# bmsMaster_conn.net
KiCad netlist of a schematic drawn in Altium Designer
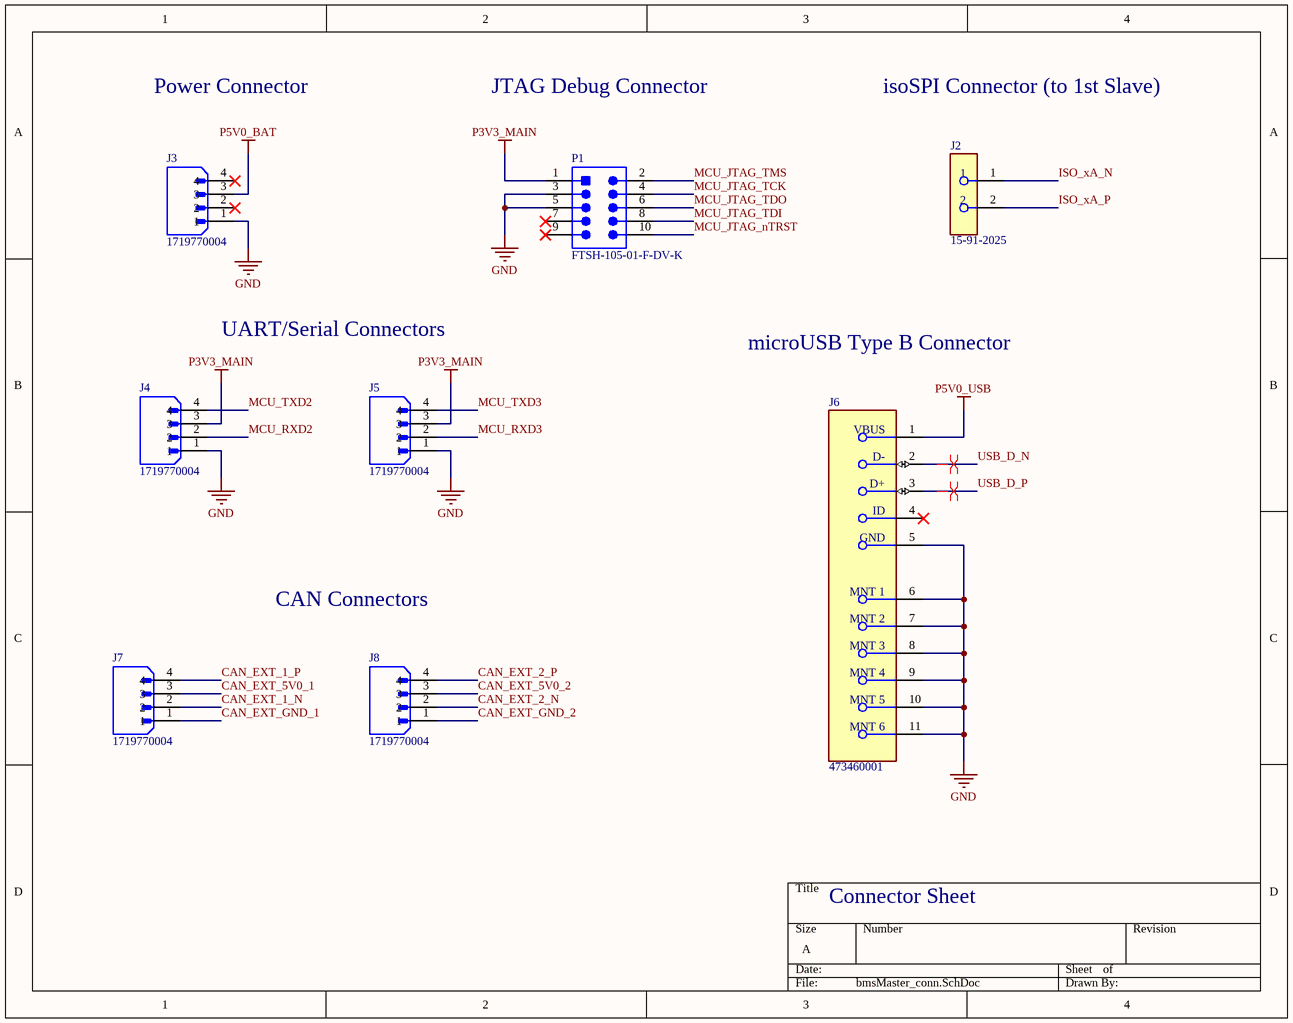
[diagram p0: bmsMaster_conn.SchDoc]

(export (version "E")
  (design (tool "Eeschema 10.0.6"))
  (components
    (comp (ref "J2")
      (value "15-91-2025")
      (footprint "FP-15-91-2025-MFG")
      (description "CONN HEADER SMD R/A 2POS 2.54MM")
      (libsource (lib "Altium Content Vault") (part "3ddab50f66188bb7952c54a1b76274c"))
    )
    (comp (ref "J3")
      (value "1719770004")
      (footprint "171977-0004:MOLEX_1719770004")
      (fields (field (name "MF") "{'manufacturer': u'Molex'}"))
      (libsource (lib "*") (part "1719770004"))
    )
    (comp (ref "J4")
      (value "1719770004")
      (footprint "171977-0004:MOLEX_1719770004")
      (fields (field (name "MF") "{'manufacturer': u'Molex'}"))
      (libsource (lib "*") (part "1719770004"))
    )
    (comp (ref "J5")
      (value "1719770004")
      (footprint "171977-0004:MOLEX_1719770004")
      (fields (field (name "MF") "{'manufacturer': u'Molex'}"))
      (libsource (lib "*") (part "1719770004"))
    )
    (comp (ref "J6")
      (value "473460001")
      (footprint "FP-473460001-MFG")
      (description "USB - micro B USB 2.0 Receptacle Connector 5 Position Surface Mount, Right Angle")
      (fields (field (name "OCTOPART") "https://octopart.com/47346-0001-molex-7164928"))
      (libsource (lib "Altium Content Vault") (part "53ae1f1d9b557310b43ca686e5bb76a"))
    )
    (comp (ref "J7")
      (value "1719770004")
      (footprint "171977-0004:MOLEX_1719770004")
      (fields (field (name "MF") "{'manufacturer': u'Molex'}"))
      (libsource (lib "*") (part "1719770004"))
    )
    (comp (ref "J8")
      (value "1719770004")
      (footprint "171977-0004:MOLEX_1719770004")
      (fields (field (name "MF") "{'manufacturer': u'Molex'}"))
      (libsource (lib "*") (part "1719770004"))
    )
    (comp (ref "P1")
      (value "FTSH-105-01-F-DV-K")
      (footprint "SMTC-FTSH-105-01-L-DV-K_V")
      (description "Male Header, Pitch 1.27 mm, 2 x 5 Position, Height 6.12 mm, RoHS, Tube")
      (fields (field (name "MANUFACTURER") "Samtec"))
      (libsource (lib "Altium Content Vault") (part "CN-2P-M-R10"))
    )
  )
  (nets
    (net (code "1") (name "/CAN_EXT_1_N") (class "Default")
      (node (ref "J7") (pin "2") (pinfunction "2_2") (pintype "passive"))
    )
    (net (code "2") (name "/CAN_EXT_1_P") (class "Default")
      (node (ref "J7") (pin "4") (pinfunction "4_4") (pintype "passive"))
    )
    (net (code "3") (name "/CAN_EXT_2_N") (class "Default")
      (node (ref "J8") (pin "2") (pinfunction "2_2") (pintype "passive"))
    )
    (net (code "4") (name "/CAN_EXT_2_P") (class "Default")
      (node (ref "J8") (pin "4") (pinfunction "4_4") (pintype "passive"))
    )
    (net (code "5") (name "/CAN_EXT_5V0_1") (class "Default")
      (node (ref "J7") (pin "3") (pinfunction "3_3") (pintype "passive"))
    )
    (net (code "6") (name "/CAN_EXT_5V0_2") (class "Default")
      (node (ref "J8") (pin "3") (pinfunction "3_3") (pintype "passive"))
    )
    (net (code "7") (name "/CAN_EXT_GND_1") (class "Default")
      (node (ref "J7") (pin "1") (pinfunction "1_1") (pintype "passive"))
    )
    (net (code "8") (name "/CAN_EXT_GND_2") (class "Default")
      (node (ref "J8") (pin "1") (pinfunction "1_1") (pintype "passive"))
    )
    (net (code "9") (name "/ISO_xA_N") (class "Default")
      (node (ref "J2") (pin "1") (pinfunction "1_1") (pintype "passive"))
    )
    (net (code "10") (name "/ISO_xA_P") (class "Default")
      (node (ref "J2") (pin "2") (pinfunction "2_2") (pintype "passive"))
    )
    (net (code "11") (name "/MCU_JTAG_TCK") (class "Default")
      (node (ref "P1") (pin "4") (pinfunction "4_4") (pintype "passive"))
    )
    (net (code "12") (name "/MCU_JTAG_TDI") (class "Default")
      (node (ref "P1") (pin "8") (pinfunction "8_8") (pintype "passive"))
    )
    (net (code "13") (name "/MCU_JTAG_TDO") (class "Default")
      (node (ref "P1") (pin "6") (pinfunction "6_6") (pintype "passive"))
    )
    (net (code "14") (name "/MCU_JTAG_TMS") (class "Default")
      (node (ref "P1") (pin "2") (pinfunction "2_2") (pintype "passive"))
    )
    (net (code "15") (name "/MCU_JTAG_nTRST") (class "Default")
      (node (ref "P1") (pin "10") (pinfunction "10_10") (pintype "passive"))
    )
    (net (code "16") (name "/MCU_RXD2") (class "Default")
      (node (ref "J4") (pin "2") (pinfunction "2_2") (pintype "passive"))
    )
    (net (code "17") (name "/MCU_RXD3") (class "Default")
      (node (ref "J5") (pin "2") (pinfunction "2_2") (pintype "passive"))
    )
    (net (code "18") (name "/MCU_TXD2") (class "Default")
      (node (ref "J4") (pin "4") (pinfunction "4_4") (pintype "passive"))
    )
    (net (code "19") (name "/MCU_TXD3") (class "Default")
      (node (ref "J5") (pin "4") (pinfunction "4_4") (pintype "passive"))
    )
    (net (code "20") (name "/USB_D_N") (class "Default")
      (node (ref "J6") (pin "2") (pinfunction "D-_2") (pintype "bidirectional"))
    )
    (net (code "21") (name "/USB_D_P") (class "Default")
      (node (ref "J6") (pin "3") (pinfunction "D+_3") (pintype "bidirectional"))
    )
    (net (code "22") (name "GND") (class "Default")
      (node (ref "J3") (pin "1") (pinfunction "1_1") (pintype "passive"))
      (node (ref "J4") (pin "1") (pinfunction "1_1") (pintype "passive"))
      (node (ref "J5") (pin "1") (pinfunction "1_1") (pintype "passive"))
      (node (ref "J6") (pin "10") (pinfunction "MNT_5_10") (pintype "passive"))
      (node (ref "J6") (pin "11") (pinfunction "MNT_6_11") (pintype "passive"))
      (node (ref "J6") (pin "5") (pinfunction "GND_5") (pintype "power_in"))
      (node (ref "J6") (pin "6") (pinfunction "MNT_1_6") (pintype "passive"))
      (node (ref "J6") (pin "7") (pinfunction "MNT_2_7") (pintype "passive"))
      (node (ref "J6") (pin "8") (pinfunction "MNT_3_8") (pintype "passive"))
      (node (ref "J6") (pin "9") (pinfunction "MNT_4_9") (pintype "passive"))
      (node (ref "P1") (pin "3") (pinfunction "3_3") (pintype "passive"))
      (node (ref "P1") (pin "5") (pinfunction "5_5") (pintype "passive"))
    )
    (net (code "23") (name "P3V3_MAIN") (class "Default")
      (node (ref "J4") (pin "3") (pinfunction "3_3") (pintype "passive"))
      (node (ref "J5") (pin "3") (pinfunction "3_3") (pintype "passive"))
      (node (ref "P1") (pin "1") (pinfunction "1_1") (pintype "passive"))
    )
    (net (code "24") (name "P5V0_BAT") (class "Default")
      (node (ref "J3") (pin "3") (pinfunction "3_3") (pintype "passive"))
    )
    (net (code "25") (name "P5V0_USB") (class "Default")
      (node (ref "J6") (pin "1") (pinfunction "VBUS_1") (pintype "power_in"))
    )
    (net (code "26") (name "unconnected-(J3-Pad2)") (class "Default")
      (node (ref "J3") (pin "2") (pinfunction "2_2") (pintype "passive+no_connect"))
    )
    (net (code "27") (name "unconnected-(J3-Pad4)") (class "Default")
      (node (ref "J3") (pin "4") (pinfunction "4_4") (pintype "passive+no_connect"))
    )
    (net (code "28") (name "unconnected-(J6-ID-Pad4)") (class "Default")
      (node (ref "J6") (pin "4") (pinfunction "ID_4") (pintype "passive+no_connect"))
    )
    (net (code "29") (name "unconnected-(P1-Pad7)") (class "Default")
      (node (ref "P1") (pin "7") (pinfunction "7_7") (pintype "passive+no_connect"))
    )
    (net (code "30") (name "unconnected-(P1-Pad9)") (class "Default")
      (node (ref "P1") (pin "9") (pinfunction "9_9") (pintype "passive+no_connect"))
    )
  )
)
